# digitalclock.net
KiCad netlist of a schematic drawn in EAGLE
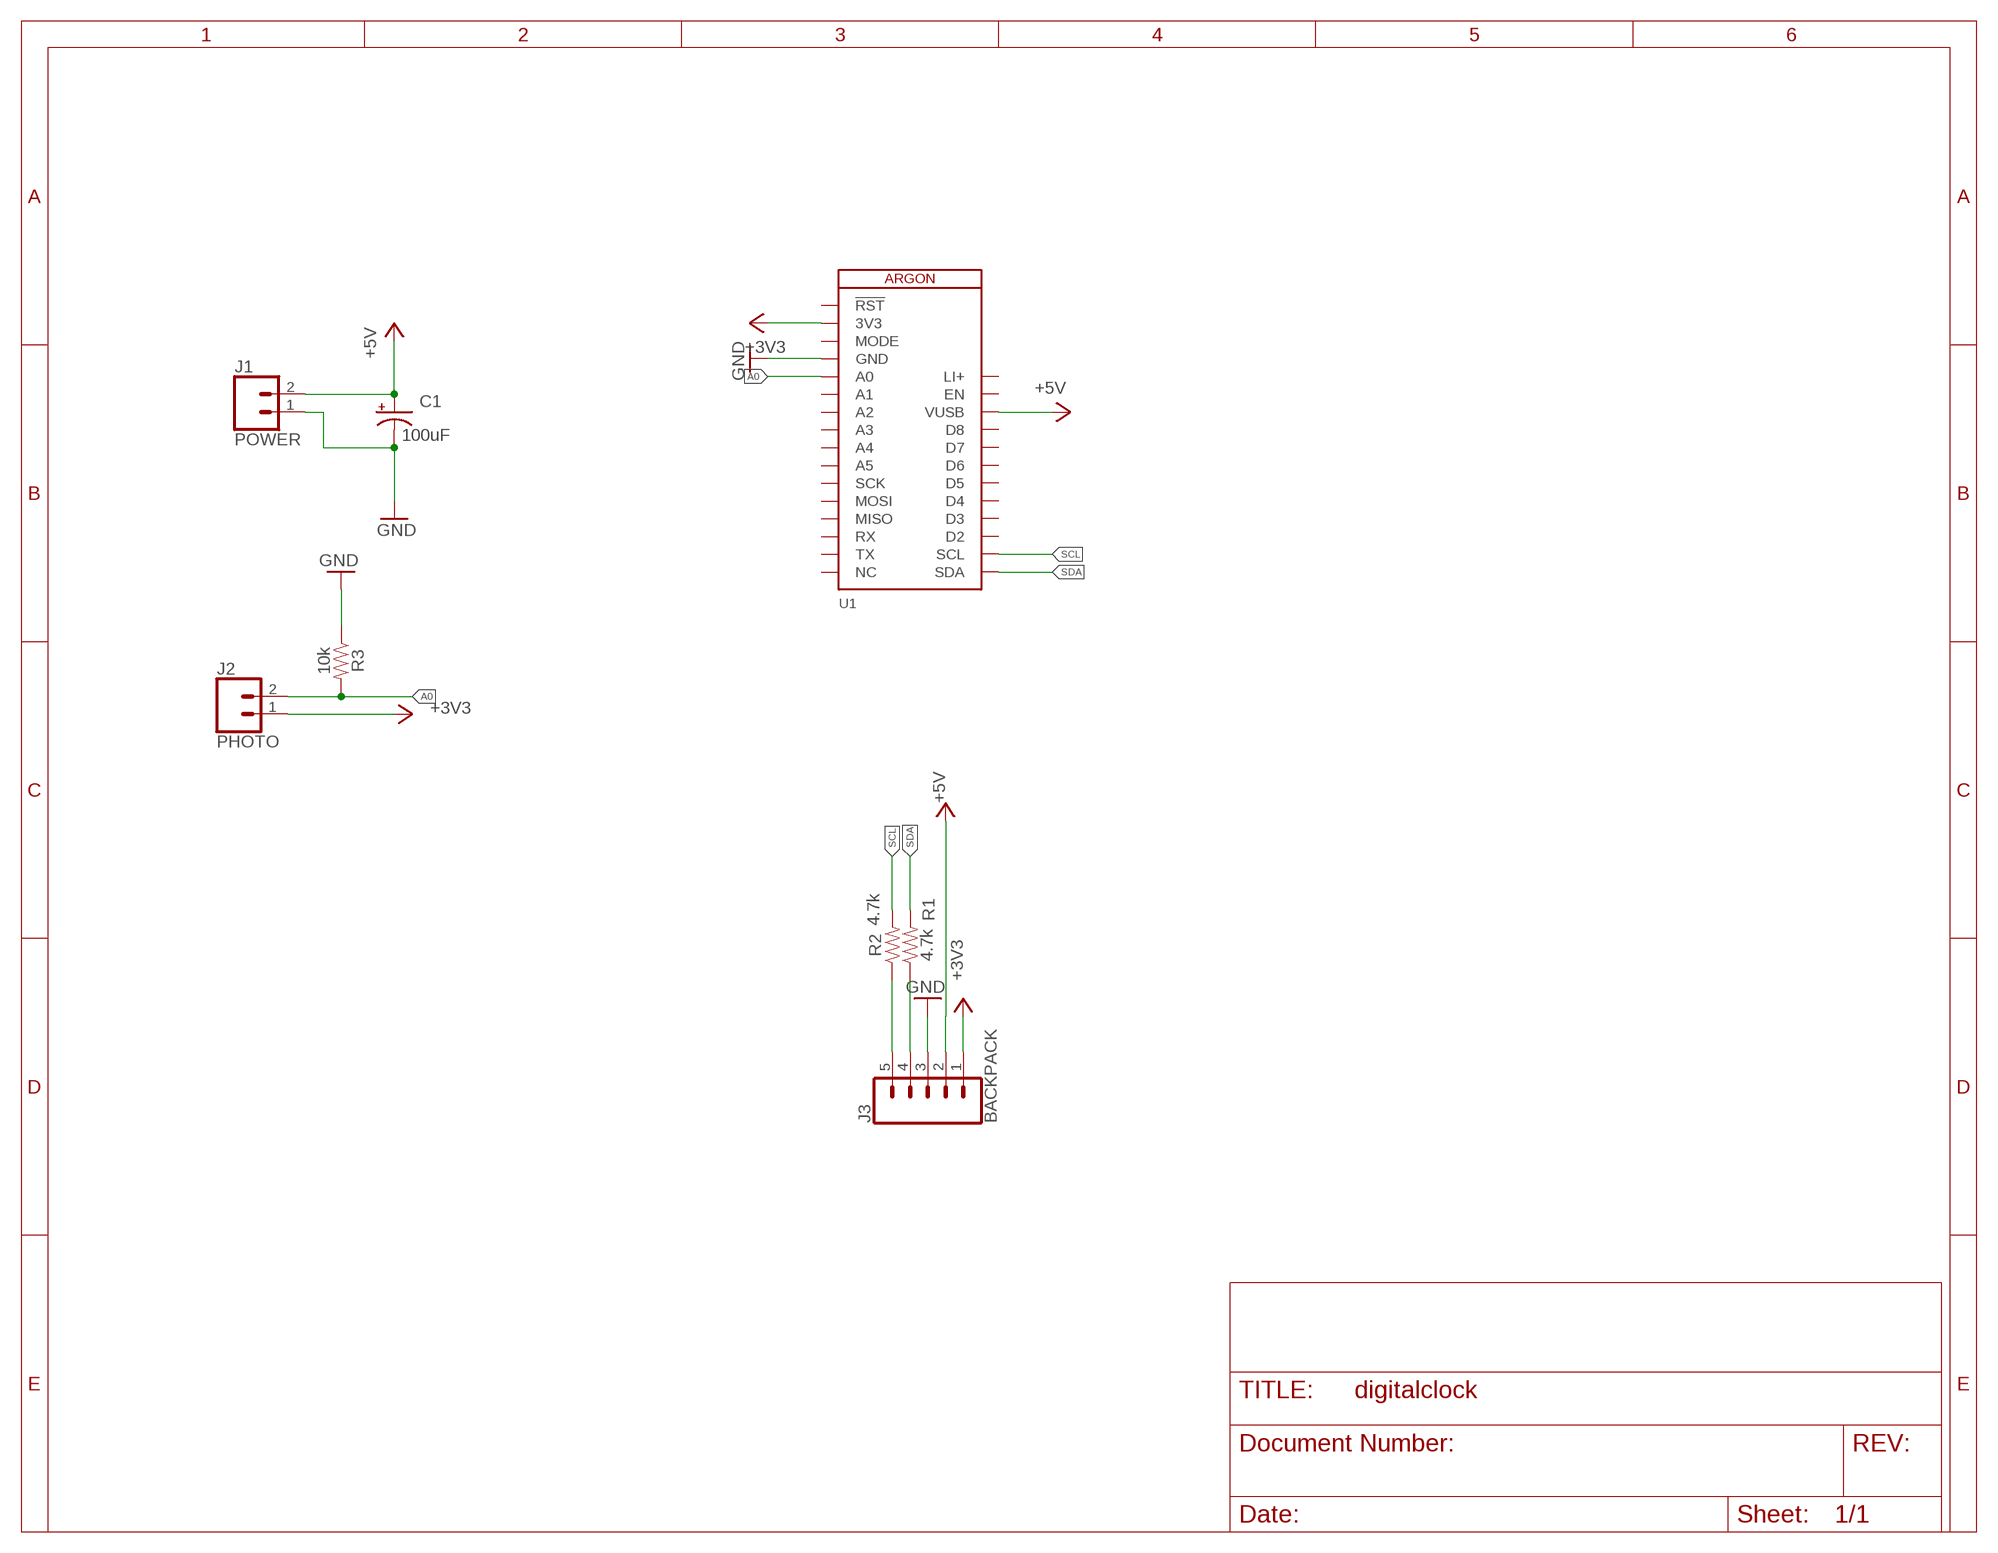
[diagram p0: schematic, sheet 1]

(export (version "E")
  (design (tool "Eeschema 10.0.6"))
  (components
    (comp (ref "C1")
      (value "100uF")
      (footprint "eagle-import:CPOL-RADIAL-2.5MM-6.5MM")
      (libsource (lib "eagle-import") (part "100UF-POLAR-RADIAL-2.5MM-25V-20%"))
    )
    (comp (ref "J1")
      (value "POWER")
      (footprint "eagle-import:1X02")
      (libsource (lib "eagle-import") (part "CONN_02"))
    )
    (comp (ref "J2")
      (value "PHOTO")
      (footprint "eagle-import:1X02")
      (libsource (lib "eagle-import") (part "CONN_02"))
    )
    (comp (ref "J3")
      (value "BACKPACK")
      (footprint "eagle-import:1X05")
      (libsource (lib "eagle-import") (part "CONN_05"))
    )
    (comp (ref "R1")
      (value "4.7k")
      (footprint "eagle-import:AXIAL-0.3")
      (libsource (lib "eagle-import") (part "1KOHM-HORIZ-1/4W-5%"))
    )
    (comp (ref "R2")
      (value "4.7k")
      (footprint "eagle-import:AXIAL-0.3")
      (libsource (lib "eagle-import") (part "1KOHM-HORIZ-1/4W-5%"))
    )
    (comp (ref "R3")
      (value "10k")
      (footprint "eagle-import:AXIAL-0.3")
      (libsource (lib "eagle-import") (part "1KOHM-HORIZ-1/4W-5%"))
    )
    (comp (ref "U1")
      (value "ARGON")
      (footprint "eagle-import:ARGON")
      (libsource (lib "eagle-import") (part "ARGON"))
    )
  )
  (nets
    (net (code "1") (name "+3V3") (class "Default")
      (node (ref "J2") (pin "1") (pinfunction "1_1") (pintype "passive"))
      (node (ref "J3") (pin "1") (pinfunction "1_1") (pintype "passive"))
      (node (ref "U1") (pin "2") (pinfunction "3V3_2") (pintype "power_in"))
    )
    (net (code "2") (name "+5V") (class "Default")
      (node (ref "C1") (pin "1") (pinfunction "+_1") (pintype "passive"))
      (node (ref "J1") (pin "2") (pinfunction "2_2") (pintype "passive"))
      (node (ref "J3") (pin "2") (pinfunction "2_2") (pintype "passive"))
      (node (ref "U1") (pin "26") (pinfunction "VUSB_26") (pintype "power_in"))
    )
    (net (code "3") (name "/LI+") (class "Default")
      (node (ref "U1") (pin "28") (pinfunction "LI+_28") (pintype "power_in"))
    )
    (net (code "4") (name "A0") (class "Default")
      (node (ref "J2") (pin "2") (pinfunction "2_2") (pintype "passive"))
      (node (ref "R3") (pin "P$2") (pinfunction "2_P$2") (pintype "passive"))
      (node (ref "U1") (pin "5") (pinfunction "A0_5") (pintype "bidirectional"))
    )
    (net (code "5") (name "GND") (class "Default")
      (node (ref "C1") (pin "2") (pinfunction "-_2") (pintype "passive"))
      (node (ref "J1") (pin "1") (pinfunction "1_1") (pintype "passive"))
      (node (ref "J3") (pin "3") (pinfunction "3_3") (pintype "passive"))
      (node (ref "R3") (pin "P$1") (pinfunction "1_P$1") (pintype "passive"))
      (node (ref "U1") (pin "4") (pinfunction "GND_4") (pintype "power_in"))
    )
    (net (code "6") (name "Net-(R1-1)") (class "Default")
      (node (ref "J3") (pin "4") (pinfunction "4_4") (pintype "passive"))
      (node (ref "R1") (pin "P$1") (pinfunction "1_P$1") (pintype "passive"))
    )
    (net (code "7") (name "Net-(R2-1)") (class "Default")
      (node (ref "J3") (pin "5") (pinfunction "5_5") (pintype "passive"))
      (node (ref "R2") (pin "P$1") (pinfunction "1_P$1") (pintype "passive"))
    )
    (net (code "8") (name "SCL") (class "Default")
      (node (ref "R2") (pin "P$2") (pinfunction "2_P$2") (pintype "passive"))
      (node (ref "U1") (pin "18") (pinfunction "SCL_18") (pintype "bidirectional"))
    )
    (net (code "9") (name "SDA") (class "Default")
      (node (ref "R1") (pin "P$2") (pinfunction "2_P$2") (pintype "passive"))
      (node (ref "U1") (pin "17") (pinfunction "SDA_17") (pintype "bidirectional"))
    )
    (net (code "10") (name "unconnected-(U1-A1-Pad6)") (class "Default")
      (node (ref "U1") (pin "6") (pinfunction "A1_6") (pintype "bidirectional"))
    )
    (net (code "11") (name "unconnected-(U1-A2-Pad7)") (class "Default")
      (node (ref "U1") (pin "7") (pinfunction "A2_7") (pintype "bidirectional"))
    )
    (net (code "12") (name "unconnected-(U1-A3-Pad8)") (class "Default")
      (node (ref "U1") (pin "8") (pinfunction "A3_8") (pintype "bidirectional"))
    )
    (net (code "13") (name "unconnected-(U1-A4-Pad9)") (class "Default")
      (node (ref "U1") (pin "9") (pinfunction "A4_9") (pintype "bidirectional"))
    )
    (net (code "14") (name "unconnected-(U1-A5-Pad10)") (class "Default")
      (node (ref "U1") (pin "10") (pinfunction "A5_10") (pintype "bidirectional"))
    )
    (net (code "15") (name "unconnected-(U1-D2-Pad19)") (class "Default")
      (node (ref "U1") (pin "19") (pinfunction "D2_19") (pintype "bidirectional"))
    )
    (net (code "16") (name "unconnected-(U1-D3-Pad20)") (class "Default")
      (node (ref "U1") (pin "20") (pinfunction "D3_20") (pintype "bidirectional"))
    )
    (net (code "17") (name "unconnected-(U1-D4-Pad21)") (class "Default")
      (node (ref "U1") (pin "21") (pinfunction "D4_21") (pintype "bidirectional"))
    )
    (net (code "18") (name "unconnected-(U1-D5-Pad22)") (class "Default")
      (node (ref "U1") (pin "22") (pinfunction "D5_22") (pintype "bidirectional"))
    )
    (net (code "19") (name "unconnected-(U1-D6-Pad23)") (class "Default")
      (node (ref "U1") (pin "23") (pinfunction "D6_23") (pintype "bidirectional"))
    )
    (net (code "20") (name "unconnected-(U1-D7-Pad24)") (class "Default")
      (node (ref "U1") (pin "24") (pinfunction "D7_24") (pintype "bidirectional"))
    )
    (net (code "21") (name "unconnected-(U1-D8-Pad25)") (class "Default")
      (node (ref "U1") (pin "25") (pinfunction "D8_25") (pintype "bidirectional"))
    )
    (net (code "22") (name "unconnected-(U1-EN-Pad27)") (class "Default")
      (node (ref "U1") (pin "27") (pinfunction "EN_27") (pintype "input"))
    )
    (net (code "23") (name "unconnected-(U1-MISO-Pad13)") (class "Default")
      (node (ref "U1") (pin "13") (pinfunction "MISO_13") (pintype "bidirectional"))
    )
    (net (code "24") (name "unconnected-(U1-MODE-Pad3)") (class "Default")
      (node (ref "U1") (pin "3") (pinfunction "MODE_3") (pintype "bidirectional"))
    )
    (net (code "25") (name "unconnected-(U1-MOSI-Pad12)") (class "Default")
      (node (ref "U1") (pin "12") (pinfunction "MOSI_12") (pintype "bidirectional"))
    )
    (net (code "26") (name "unconnected-(U1-NC-Pad16)") (class "Default")
      (node (ref "U1") (pin "16") (pinfunction "NC_16") (pintype "bidirectional"))
    )
    (net (code "27") (name "unconnected-(U1-RX-Pad14)") (class "Default")
      (node (ref "U1") (pin "14") (pinfunction "RX_14") (pintype "bidirectional"))
    )
    (net (code "28") (name "unconnected-(U1-SCK-Pad11)") (class "Default")
      (node (ref "U1") (pin "11") (pinfunction "SCK_11") (pintype "bidirectional"))
    )
    (net (code "29") (name "unconnected-(U1-TX-Pad15)") (class "Default")
      (node (ref "U1") (pin "15") (pinfunction "TX_15") (pintype "bidirectional"))
    )
    (net (code "30") (name "unconnected-(U1-~{RST}-Pad1)") (class "Default")
      (node (ref "U1") (pin "1") (pinfunction "~{RST}_1") (pintype "input"))
    )
  )
)
